# TASK1_2_SCH.net
KiCad netlist of a schematic drawn in Altium Designer
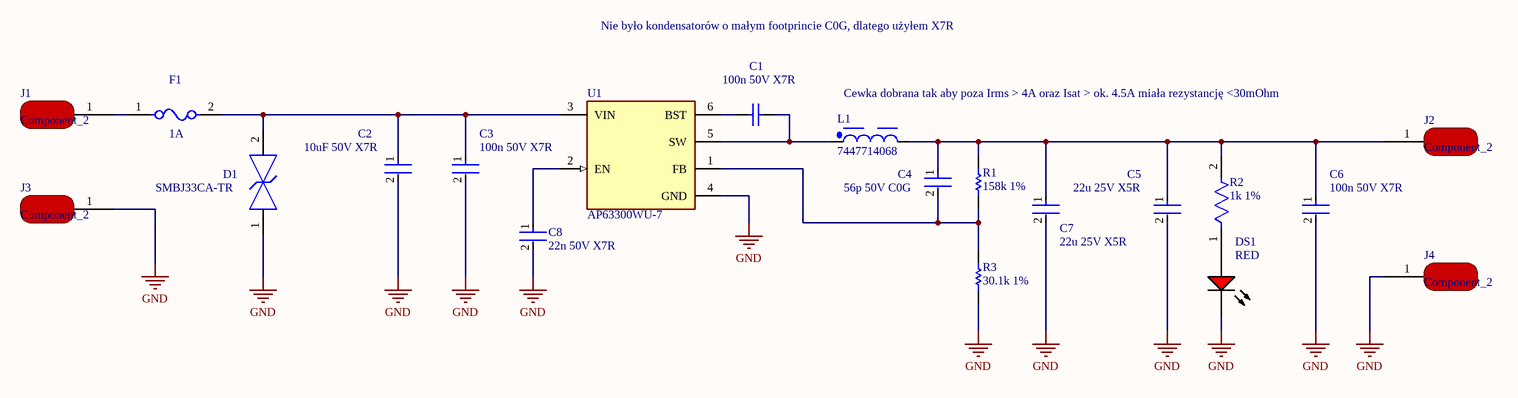
[diagram p0: TASK1.2_SCH.SchDoc]

(export (version "E")
  (design (tool "Eeschema 10.0.6"))
  (components
    (comp (ref "C1")
      (value "100n 50V X7R")
      (footprint "CAPC1608X90X35ML10T15")
      (description "Chip Capacitor, 0.1 uF, +/- 10%, 50 V, -55 to 125 degC, 0603 (1608 Metric), RoHS, Tape and Reel")
      (fields (field (name "TOLERANCE") "10%") (field (name "VOLTAGE") "50V"))
      (libsource (lib "Altium Content Vault") (part "CAP-NP-2"))
    )
    (comp (ref "C2")
      (value "10uF 50V X7R")
      (footprint "FP-MK325A-MFG")
      (description "CAP CER 10UF 50V X7R 1210")
      (fields (field (name "TOLERANCE") "10%"))
      (libsource (lib "Altium Content Vault") (part "b4654b650e69147ec39a6b967a45e02"))
    )
    (comp (ref "C3")
      (value "100n 50V X7R")
      (footprint "FP-CGA3E-0_3-0_1-IPC_A")
      (description "Cap Ceramic 100nF 50V X7R 10% Pad SMD 0603 +125°C Automotive T/R")
      (fields (field (name "TOLERANCE") "10%") (field (name "VOLTAGE") "50V"))
      (libsource (lib "Altium Content Vault") (part "b4654b650e69147ec39a6b967a45e02"))
    )
    (comp (ref "C4")
      (value "56p 50V C0G")
      (footprint "FP-C0603C-CF-MFG")
      (description "CAP CER 56PF 50V 1% NP0 0603")
      (fields (field (name "TOLERANCE") "0.01") (field (name "MANUFACTURER") "KEMET"))
      (libsource (lib "Altium Content Vault") (part "b4654b650e69147ec39a6b967a45e02"))
    )
    (comp (ref "C5")
      (value "22u 25V X5R")
      (footprint "FP-C3216-160-0_2-IPC_B")
      (description "Multilayer Ceramic Capacitors 22uF ±20% 25V X5R SMD 1206")
      (fields (field (name "TOLERANCE") "20%"))
      (libsource (lib "Altium Content Vault") (part "11868f565c42a9108669ba33697ecf6"))
    )
    (comp (ref "C6")
      (value "100n 50V X7R")
      (footprint "FP-CGA3E-0_3-0_1-IPC_A")
      (description "Cap Ceramic 100nF 50V X7R 10% Pad SMD 0603 +125°C Automotive T/R")
      (fields (field (name "TOLERANCE") "10%") (field (name "VOLTAGE") "50V"))
      (libsource (lib "Altium Content Vault") (part "b4654b650e69147ec39a6b967a45e02"))
    )
    (comp (ref "C7")
      (value "22u 25V X5R")
      (footprint "FP-C3216-160-0_2-IPC_B")
      (description "Multilayer Ceramic Capacitors 22uF ±20% 25V X5R SMD 1206")
      (fields (field (name "TOLERANCE") "20%"))
      (libsource (lib "Altium Content Vault") (part "11868f565c42a9108669ba33697ecf6"))
    )
    (comp (ref "C8")
      (value "22n 50V X7R")
      (footprint "FP-CC0603-DA-MFG")
      (description "CAP CER 0.022UF 50V X7R 0603")
      (fields (field (name "TOLERANCE") "10%") (field (name "VOLTAGE") "50V"))
      (libsource (lib "Altium Content Vault") (part "11868f565c42a9108669ba33697ecf6"))
    )
    (comp (ref "D1")
      (value "SMBJ33CA-TR")
      (footprint "FP-SMB-CA-MFG")
      (description "TVS DIODE 33V 69.7V SMB")
      (fields
        (field (name "OCTOPART") "https://octopart.com/smbj33ca-tr-stmicroelectronics-347069")
        (field (name "MANUFACTURER") "STMicroelectronics")
      )
      (libsource (lib "Altium Content Vault") (part "11bd9d59d340f0612179daf16ad9b72"))
    )
    (comp (ref "DS1")
      (value "RED")
      (footprint "AVAG-HSMX-C190_V")
      (description "LED Uni-Color Red, 52 mW, 20 mA, -40 to 85 degC, 2-Pin SMD, RoHS, Tape and Reel")
      (fields (field (name "MANUFACTURER") "Avago"))
      (libsource (lib "Altium Content Vault") (part "LED-RED-AK-2"))
    )
    (comp (ref "F1")
      (value "1A")
      (footprint "FP-0468-MFG")
      (description "FUSE BOARD MNT 1A 63VAC/VDC 1206")
      (fields
        (field (name "MANUFACTURER") "Littelfuse")
        (field (name "OCTOPART") "https://octopart.com/0468001.nr-littelfuse-566477")
      )
      (libsource (lib "Altium Content Vault") (part "5bcf9b9f640e542cf0359d10258e979"))
    )
    (comp (ref "J1")
      (value "Component_2")
      (footprint "SMD PAD 3x2mm")
      (libsource (lib "TASK1.2_Schlib") (part "Component_2"))
    )
    (comp (ref "J2")
      (value "Component_2")
      (footprint "SMD PAD 3x2mm")
      (libsource (lib "TASK1.2_Schlib") (part "Component_2"))
    )
    (comp (ref "J3")
      (value "Component_2")
      (footprint "SMD PAD 3x2mm")
      (libsource (lib "TASK1.2_Schlib") (part "Component_2"))
    )
    (comp (ref "J4")
      (value "Component_2")
      (footprint "SMD PAD 3x2mm")
      (libsource (lib "TASK1.2_Schlib") (part "Component_2"))
    )
    (comp (ref "L1")
      (value "7447714068")
      (footprint "WE-PD_1050P")
      (description "7447714068\r\n6.8UH 5.2A 22 MOHM SMD, ISAT 5.8A")
      (fields (field (name "TOLERANCE") "30%"))
      (libsource (lib "Altium Content Vault") (part "Inductor - 2"))
    )
    (comp (ref "R1")
      (value "158k 1%")
      (footprint "RESC1005X40X25ML05T05")
      (fields (field (name "MANUFACTURER") "Panasonic") (field (name "PART NUMBER") "ERJ-2RKF1583X"))
      (libsource (lib "Altium Content Vault") (part "RES"))
    )
    (comp (ref "R2")
      (value "1k 1%")
      (footprint "FP-RC0402-0_4-IPC_A")
      (description "RES 1K OHM 1% 1/16W 0402")
      (fields (field (name "TOLERANCE") "1%"))
      (libsource (lib "Altium Content Vault") (part "1029c3af85768c4190bb7ad29bc67b5"))
    )
    (comp (ref "R3")
      (value "30.1k 1%")
      (footprint "RESC1005X35X20NL05T10")
      (fields
        (field (name "MANUFACTURER") "TE Connectivity / AMP")
        (field (name "PART NUMBER") "CPF0402B30K1E1")
      )
      (libsource (lib "Altium Content Vault") (part "RES"))
    )
    (comp (ref "U1")
      (value "AP63300WU-7")
      (footprint "FP-TSOT26-IPC_A")
      (description "DCDC CONV HV BUCK TSOT26")
      (libsource (lib "Altium Content Vault") (part "1f55634e5cdcb17378ea3938d0fe863"))
    )
  )
  (nets
    (net (code "1") (name "GND") (class "Default")
      (node (ref "C2") (pin "2") (pinfunction "2_2") (pintype "passive"))
      (node (ref "C3") (pin "2") (pinfunction "2_2") (pintype "passive"))
      (node (ref "C5") (pin "2") (pinfunction "2_2") (pintype "passive"))
      (node (ref "C6") (pin "2") (pinfunction "2_2") (pintype "passive"))
      (node (ref "C7") (pin "2") (pinfunction "2_2") (pintype "passive"))
      (node (ref "C8") (pin "2") (pinfunction "2_2") (pintype "passive"))
      (node (ref "D1") (pin "1") (pinfunction "1_1") (pintype "passive"))
      (node (ref "DS1") (pin "2") (pinfunction "K_2") (pintype "passive"))
      (node (ref "J3") (pin "1") (pintype "passive"))
      (node (ref "J4") (pin "1") (pintype "passive"))
      (node (ref "R3") (pin "1") (pinfunction "1_1") (pintype "passive"))
      (node (ref "U1") (pin "4") (pinfunction "GND_4") (pintype "power_in"))
    )
    (net (code "2") (name "Net-(C4-Pad1)") (class "Default")
      (node (ref "C4") (pin "1") (pinfunction "1_1") (pintype "passive"))
      (node (ref "C5") (pin "1") (pinfunction "1_1") (pintype "passive"))
      (node (ref "C6") (pin "1") (pinfunction "1_1") (pintype "passive"))
      (node (ref "C7") (pin "1") (pinfunction "1_1") (pintype "passive"))
      (node (ref "J2") (pin "1") (pintype "passive"))
      (node (ref "L1") (pin "2") (pinfunction "2_2") (pintype "passive"))
      (node (ref "R1") (pin "2") (pinfunction "2_2") (pintype "passive"))
      (node (ref "R2") (pin "2") (pinfunction "2_2") (pintype "passive"))
    )
    (net (code "3") (name "Net-(DS1-A)") (class "Default")
      (node (ref "DS1") (pin "1") (pinfunction "A_1") (pintype "passive"))
      (node (ref "R2") (pin "1") (pinfunction "1_1") (pintype "passive"))
    )
    (net (code "4") (name "Net-(F1-Pad1)") (class "Default")
      (node (ref "F1") (pin "1") (pinfunction "1_1") (pintype "passive"))
      (node (ref "J1") (pin "1") (pintype "passive"))
    )
    (net (code "5") (name "Net-(U1-BST)") (class "Default")
      (node (ref "C1") (pin "1") (pinfunction "1_1") (pintype "passive"))
      (node (ref "U1") (pin "6") (pinfunction "BST_6") (pintype "passive"))
    )
    (net (code "6") (name "Net-(U1-EN)") (class "Default")
      (node (ref "C8") (pin "1") (pinfunction "1_1") (pintype "passive"))
      (node (ref "U1") (pin "2") (pinfunction "EN_2") (pintype "input"))
    )
    (net (code "7") (name "Net-(U1-FB)") (class "Default")
      (node (ref "C4") (pin "2") (pinfunction "2_2") (pintype "passive"))
      (node (ref "R1") (pin "1") (pinfunction "1_1") (pintype "passive"))
      (node (ref "R3") (pin "2") (pinfunction "2_2") (pintype "passive"))
      (node (ref "U1") (pin "1") (pinfunction "FB_1") (pintype "passive"))
    )
    (net (code "8") (name "Net-(U1-SW)") (class "Default")
      (node (ref "C1") (pin "2") (pinfunction "2_2") (pintype "passive"))
      (node (ref "L1") (pin "1") (pinfunction "1_1") (pintype "passive"))
      (node (ref "U1") (pin "5") (pinfunction "SW_5") (pintype "passive"))
    )
    (net (code "9") (name "Net-(U1-VIN)") (class "Default")
      (node (ref "C2") (pin "1") (pinfunction "1_1") (pintype "passive"))
      (node (ref "C3") (pin "1") (pinfunction "1_1") (pintype "passive"))
      (node (ref "D1") (pin "2") (pinfunction "2_2") (pintype "passive"))
      (node (ref "F1") (pin "2") (pinfunction "2_2") (pintype "passive"))
      (node (ref "U1") (pin "3") (pinfunction "VIN_3") (pintype "power_in"))
    )
  )
)
